# encoder.net
KiCad netlist of a schematic drawn in EAGLE
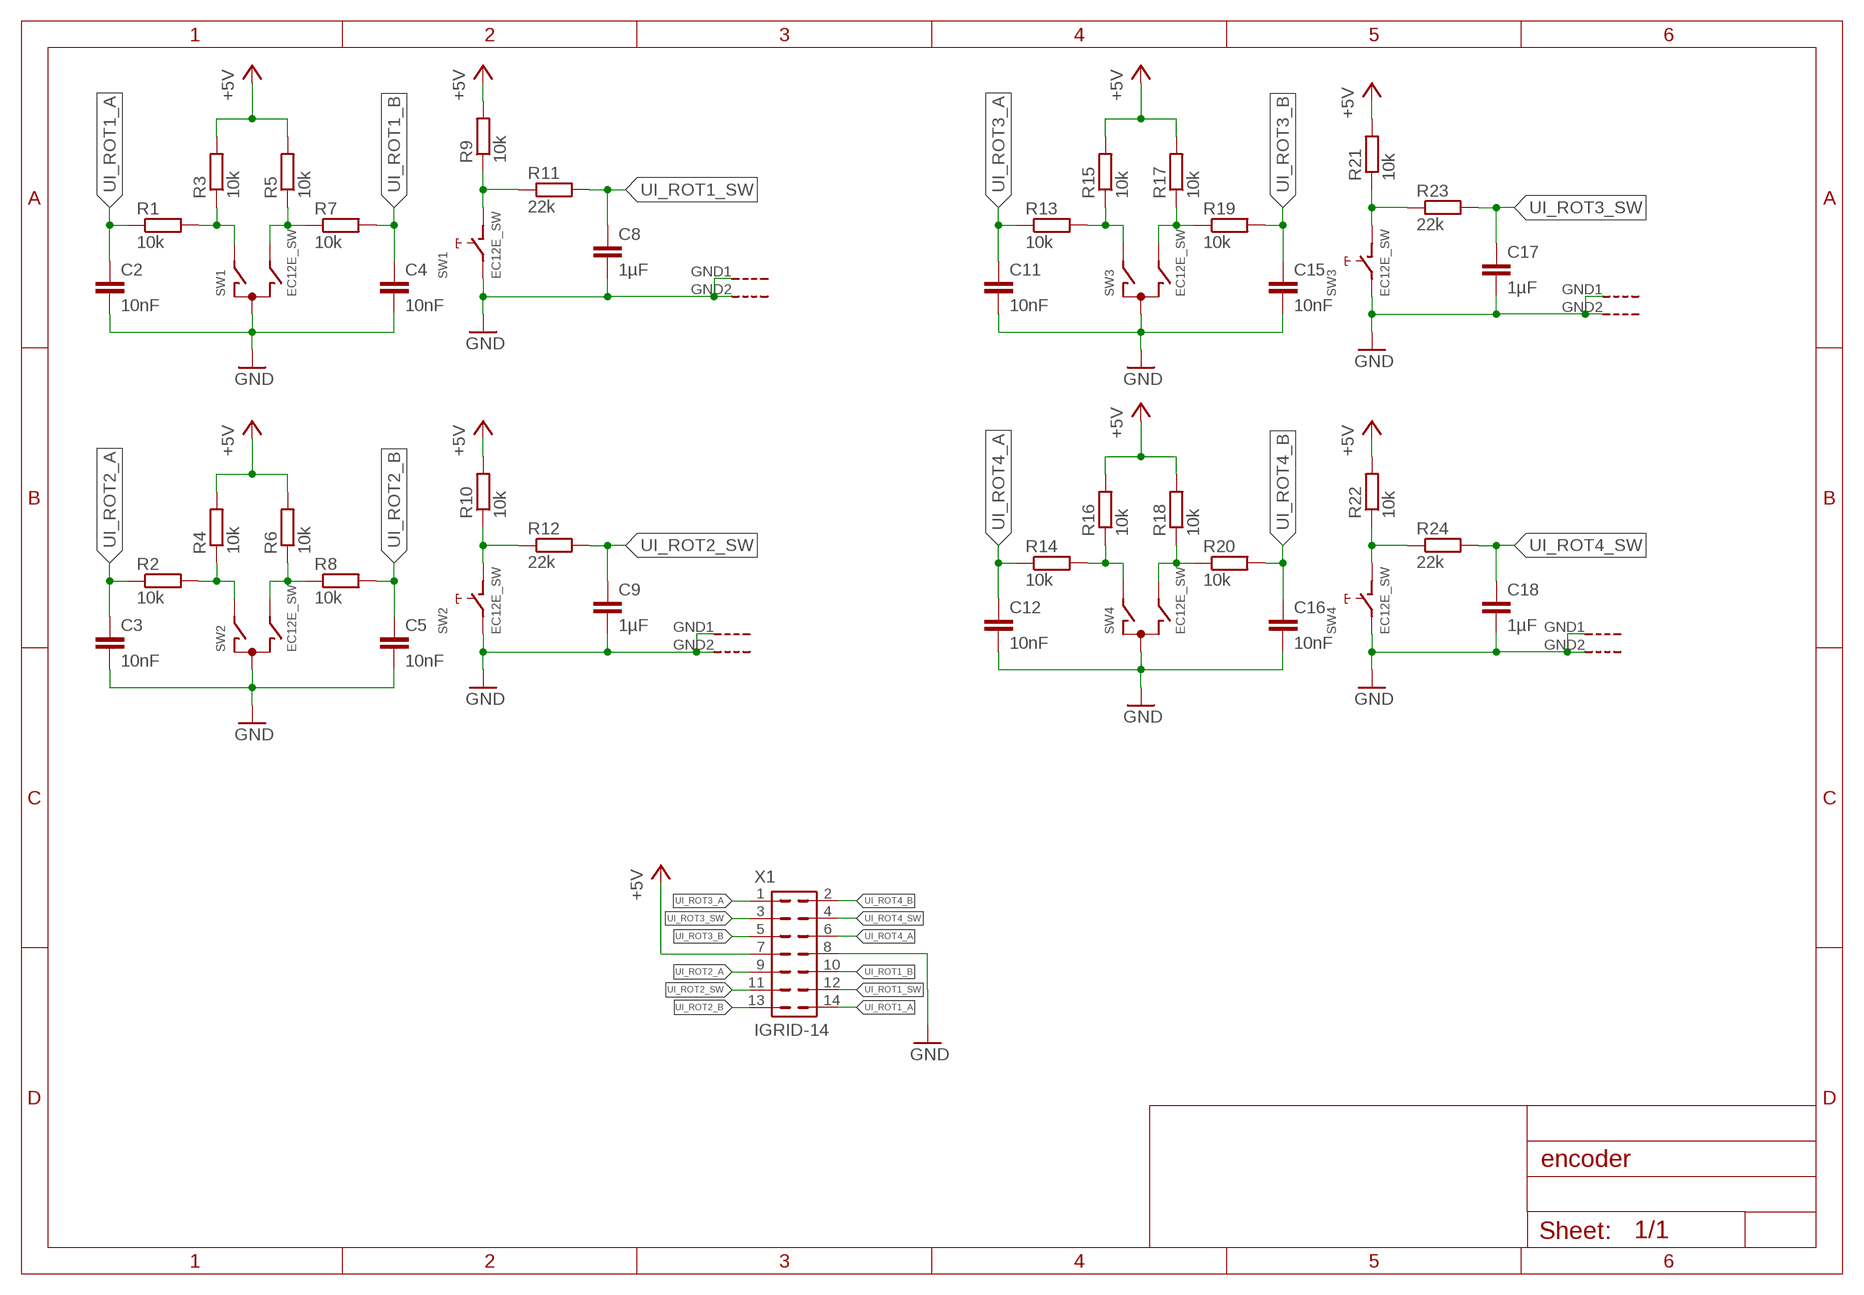
[diagram p0: schematic, sheet 1]

(export (version "E")
  (design (tool "Eeschema 10.0.6"))
  (components
    (comp (ref "C2")
      (value "10nF")
      (footprint "eagle-import:C0805")
      (libsource (lib "eagle-import") (part "C-EUC0805"))
    )
    (comp (ref "C3")
      (value "10nF")
      (footprint "eagle-import:C0805")
      (libsource (lib "eagle-import") (part "C-EUC0805"))
    )
    (comp (ref "C4")
      (value "10nF")
      (footprint "eagle-import:C0805")
      (libsource (lib "eagle-import") (part "C-EUC0805"))
    )
    (comp (ref "C5")
      (value "10nF")
      (footprint "eagle-import:C0805")
      (libsource (lib "eagle-import") (part "C-EUC0805"))
    )
    (comp (ref "C8")
      (value "1µF")
      (footprint "eagle-import:C0805")
      (libsource (lib "eagle-import") (part "C-EUC0805"))
    )
    (comp (ref "C9")
      (value "1µF")
      (footprint "eagle-import:C0805")
      (libsource (lib "eagle-import") (part "C-EUC0805"))
    )
    (comp (ref "C11")
      (value "10nF")
      (footprint "eagle-import:C0805")
      (libsource (lib "eagle-import") (part "C-EUC0805"))
    )
    (comp (ref "C12")
      (value "10nF")
      (footprint "eagle-import:C0805")
      (libsource (lib "eagle-import") (part "C-EUC0805"))
    )
    (comp (ref "C15")
      (value "10nF")
      (footprint "eagle-import:C0805")
      (libsource (lib "eagle-import") (part "C-EUC0805"))
    )
    (comp (ref "C16")
      (value "10nF")
      (footprint "eagle-import:C0805")
      (libsource (lib "eagle-import") (part "C-EUC0805"))
    )
    (comp (ref "C17")
      (value "1µF")
      (footprint "eagle-import:C0805")
      (libsource (lib "eagle-import") (part "C-EUC0805"))
    )
    (comp (ref "C18")
      (value "1µF")
      (footprint "eagle-import:C0805")
      (libsource (lib "eagle-import") (part "C-EUC0805"))
    )
    (comp (ref "R1")
      (value "10k")
      (footprint "eagle-import:R0805")
      (libsource (lib "eagle-import") (part "R-EU_R0805"))
    )
    (comp (ref "R2")
      (value "10k")
      (footprint "eagle-import:R0805")
      (libsource (lib "eagle-import") (part "R-EU_R0805"))
    )
    (comp (ref "R3")
      (value "10k")
      (footprint "eagle-import:R0805")
      (libsource (lib "eagle-import") (part "R-EU_R0805"))
    )
    (comp (ref "R4")
      (value "10k")
      (footprint "eagle-import:R0805")
      (libsource (lib "eagle-import") (part "R-EU_R0805"))
    )
    (comp (ref "R5")
      (value "10k")
      (footprint "eagle-import:R0805")
      (libsource (lib "eagle-import") (part "R-EU_R0805"))
    )
    (comp (ref "R6")
      (value "10k")
      (footprint "eagle-import:R0805")
      (libsource (lib "eagle-import") (part "R-EU_R0805"))
    )
    (comp (ref "R7")
      (value "10k")
      (footprint "eagle-import:R0805")
      (libsource (lib "eagle-import") (part "R-EU_R0805"))
    )
    (comp (ref "R8")
      (value "10k")
      (footprint "eagle-import:R0805")
      (libsource (lib "eagle-import") (part "R-EU_R0805"))
    )
    (comp (ref "R9")
      (value "10k")
      (footprint "eagle-import:R0805")
      (libsource (lib "eagle-import") (part "R-EU_R0805"))
    )
    (comp (ref "R10")
      (value "10k")
      (footprint "eagle-import:R0805")
      (libsource (lib "eagle-import") (part "R-EU_R0805"))
    )
    (comp (ref "R11")
      (value "22k")
      (footprint "eagle-import:R0805")
      (libsource (lib "eagle-import") (part "R-EU_R0805"))
    )
    (comp (ref "R12")
      (value "22k")
      (footprint "eagle-import:R0805")
      (libsource (lib "eagle-import") (part "R-EU_R0805"))
    )
    (comp (ref "R13")
      (value "10k")
      (footprint "eagle-import:R0805")
      (libsource (lib "eagle-import") (part "R-EU_R0805"))
    )
    (comp (ref "R14")
      (value "10k")
      (footprint "eagle-import:R0805")
      (libsource (lib "eagle-import") (part "R-EU_R0805"))
    )
    (comp (ref "R15")
      (value "10k")
      (footprint "eagle-import:R0805")
      (libsource (lib "eagle-import") (part "R-EU_R0805"))
    )
    (comp (ref "R16")
      (value "10k")
      (footprint "eagle-import:R0805")
      (libsource (lib "eagle-import") (part "R-EU_R0805"))
    )
    (comp (ref "R17")
      (value "10k")
      (footprint "eagle-import:R0805")
      (libsource (lib "eagle-import") (part "R-EU_R0805"))
    )
    (comp (ref "R18")
      (value "10k")
      (footprint "eagle-import:R0805")
      (libsource (lib "eagle-import") (part "R-EU_R0805"))
    )
    (comp (ref "R19")
      (value "10k")
      (footprint "eagle-import:R0805")
      (libsource (lib "eagle-import") (part "R-EU_R0805"))
    )
    (comp (ref "R20")
      (value "10k")
      (footprint "eagle-import:R0805")
      (libsource (lib "eagle-import") (part "R-EU_R0805"))
    )
    (comp (ref "R21")
      (value "10k")
      (footprint "eagle-import:R0805")
      (libsource (lib "eagle-import") (part "R-EU_R0805"))
    )
    (comp (ref "R22")
      (value "10k")
      (footprint "eagle-import:R0805")
      (libsource (lib "eagle-import") (part "R-EU_R0805"))
    )
    (comp (ref "R23")
      (value "22k")
      (footprint "eagle-import:R0805")
      (libsource (lib "eagle-import") (part "R-EU_R0805"))
    )
    (comp (ref "R24")
      (value "22k")
      (footprint "eagle-import:R0805")
      (libsource (lib "eagle-import") (part "R-EU_R0805"))
    )
    (comp (ref "SW1")
      (value "EC12E_SW")
      (footprint "eagle-import:ALPS_EC12E_SW")
      (fields (field (name "MPN") "EC12E2424407"))
      (libsource (lib "eagle-import") (part "EC12E_SW"))
    )
    (comp (ref "SW2")
      (value "EC12E_SW")
      (footprint "eagle-import:ALPS_EC12E_SW")
      (fields (field (name "MPN") "EC12E2424407"))
      (libsource (lib "eagle-import") (part "EC12E_SW"))
    )
    (comp (ref "SW3")
      (value "EC12E_SW")
      (footprint "eagle-import:ALPS_EC12E_SW")
      (fields (field (name "MPN") "EC12E2424407"))
      (libsource (lib "eagle-import") (part "EC12E_SW"))
    )
    (comp (ref "SW4")
      (value "EC12E_SW")
      (footprint "eagle-import:ALPS_EC12E_SW")
      (fields (field (name "MPN") "EC12E2424407"))
      (libsource (lib "eagle-import") (part "EC12E_SW"))
    )
    (comp (ref "X1")
      (value "IGRID-14")
      (footprint "eagle-import:I-GRID-14")
      (libsource (lib "eagle-import") (part "IGRID-14"))
    )
  )
  (nets
    (net (code "1") (name "+5V") (class "Default")
      (node (ref "R10") (pin "2") (pinfunction "2_2") (pintype "passive"))
      (node (ref "R15") (pin "2") (pinfunction "2_2") (pintype "passive"))
      (node (ref "R16") (pin "2") (pinfunction "2_2") (pintype "passive"))
      (node (ref "R17") (pin "2") (pinfunction "2_2") (pintype "passive"))
      (node (ref "R18") (pin "2") (pinfunction "2_2") (pintype "passive"))
      (node (ref "R21") (pin "2") (pinfunction "2_2") (pintype "passive"))
      (node (ref "R22") (pin "2") (pinfunction "2_2") (pintype "passive"))
      (node (ref "R3") (pin "2") (pinfunction "2_2") (pintype "passive"))
      (node (ref "R4") (pin "2") (pinfunction "2_2") (pintype "passive"))
      (node (ref "R5") (pin "2") (pinfunction "2_2") (pintype "passive"))
      (node (ref "R6") (pin "2") (pinfunction "2_2") (pintype "passive"))
      (node (ref "R9") (pin "2") (pinfunction "2_2") (pintype "passive"))
      (node (ref "X1") (pin "7") (pinfunction "7_7") (pintype "passive"))
    )
    (net (code "2") (name "GND") (class "Default")
      (node (ref "C11") (pin "2") (pinfunction "2_2") (pintype "passive"))
      (node (ref "C12") (pin "2") (pinfunction "2_2") (pintype "passive"))
      (node (ref "C15") (pin "2") (pinfunction "2_2") (pintype "passive"))
      (node (ref "C16") (pin "2") (pinfunction "2_2") (pintype "passive"))
      (node (ref "C17") (pin "2") (pinfunction "2_2") (pintype "passive"))
      (node (ref "C18") (pin "2") (pinfunction "2_2") (pintype "passive"))
      (node (ref "C2") (pin "2") (pinfunction "2_2") (pintype "passive"))
      (node (ref "C3") (pin "2") (pinfunction "2_2") (pintype "passive"))
      (node (ref "C4") (pin "2") (pinfunction "2_2") (pintype "passive"))
      (node (ref "C5") (pin "2") (pinfunction "2_2") (pintype "passive"))
      (node (ref "C8") (pin "2") (pinfunction "2_2") (pintype "passive"))
      (node (ref "C9") (pin "2") (pinfunction "2_2") (pintype "passive"))
      (node (ref "SW1") (pin "C") (pinfunction "C_C") (pintype "passive"))
      (node (ref "SW1") (pin "E") (pinfunction "2_E") (pintype "passive"))
      (node (ref "SW1") (pin "GND1") (pinfunction "G_GND1") (pintype "passive"))
      (node (ref "SW1") (pin "GND2") (pinfunction "G_GND2") (pintype "passive"))
      (node (ref "SW2") (pin "C") (pinfunction "C_C") (pintype "passive"))
      (node (ref "SW2") (pin "E") (pinfunction "2_E") (pintype "passive"))
      (node (ref "SW2") (pin "GND1") (pinfunction "G_GND1") (pintype "passive"))
      (node (ref "SW2") (pin "GND2") (pinfunction "G_GND2") (pintype "passive"))
      (node (ref "SW3") (pin "C") (pinfunction "C_C") (pintype "passive"))
      (node (ref "SW3") (pin "E") (pinfunction "2_E") (pintype "passive"))
      (node (ref "SW3") (pin "GND1") (pinfunction "G_GND1") (pintype "passive"))
      (node (ref "SW3") (pin "GND2") (pinfunction "G_GND2") (pintype "passive"))
      (node (ref "SW4") (pin "C") (pinfunction "C_C") (pintype "passive"))
      (node (ref "SW4") (pin "E") (pinfunction "2_E") (pintype "passive"))
      (node (ref "SW4") (pin "GND1") (pinfunction "G_GND1") (pintype "passive"))
      (node (ref "SW4") (pin "GND2") (pinfunction "G_GND2") (pintype "passive"))
      (node (ref "X1") (pin "8") (pinfunction "8_8") (pintype "passive"))
    )
    (net (code "3") (name "Net-(R1-Pad2)") (class "Default")
      (node (ref "R1") (pin "2") (pinfunction "2_2") (pintype "passive"))
      (node (ref "R3") (pin "1") (pinfunction "1_1") (pintype "passive"))
      (node (ref "SW1") (pin "A") (pinfunction "A_A") (pintype "passive"))
    )
    (net (code "4") (name "Net-(R2-Pad2)") (class "Default")
      (node (ref "R2") (pin "2") (pinfunction "2_2") (pintype "passive"))
      (node (ref "R4") (pin "1") (pinfunction "1_1") (pintype "passive"))
      (node (ref "SW2") (pin "A") (pinfunction "A_A") (pintype "passive"))
    )
    (net (code "5") (name "Net-(R5-Pad1)") (class "Default")
      (node (ref "R5") (pin "1") (pinfunction "1_1") (pintype "passive"))
      (node (ref "R7") (pin "1") (pinfunction "1_1") (pintype "passive"))
      (node (ref "SW1") (pin "B") (pinfunction "B_B") (pintype "passive"))
    )
    (net (code "6") (name "Net-(R6-Pad1)") (class "Default")
      (node (ref "R6") (pin "1") (pinfunction "1_1") (pintype "passive"))
      (node (ref "R8") (pin "1") (pinfunction "1_1") (pintype "passive"))
      (node (ref "SW2") (pin "B") (pinfunction "B_B") (pintype "passive"))
    )
    (net (code "7") (name "Net-(R13-Pad2)") (class "Default")
      (node (ref "R13") (pin "2") (pinfunction "2_2") (pintype "passive"))
      (node (ref "R15") (pin "1") (pinfunction "1_1") (pintype "passive"))
      (node (ref "SW3") (pin "A") (pinfunction "A_A") (pintype "passive"))
    )
    (net (code "8") (name "Net-(R14-Pad2)") (class "Default")
      (node (ref "R14") (pin "2") (pinfunction "2_2") (pintype "passive"))
      (node (ref "R16") (pin "1") (pinfunction "1_1") (pintype "passive"))
      (node (ref "SW4") (pin "A") (pinfunction "A_A") (pintype "passive"))
    )
    (net (code "9") (name "Net-(R17-Pad1)") (class "Default")
      (node (ref "R17") (pin "1") (pinfunction "1_1") (pintype "passive"))
      (node (ref "R19") (pin "1") (pinfunction "1_1") (pintype "passive"))
      (node (ref "SW3") (pin "B") (pinfunction "B_B") (pintype "passive"))
    )
    (net (code "10") (name "Net-(R18-Pad1)") (class "Default")
      (node (ref "R18") (pin "1") (pinfunction "1_1") (pintype "passive"))
      (node (ref "R20") (pin "1") (pinfunction "1_1") (pintype "passive"))
      (node (ref "SW4") (pin "B") (pinfunction "B_B") (pintype "passive"))
    )
    (net (code "11") (name "Net-(SW1B-1)") (class "Default")
      (node (ref "R11") (pin "1") (pinfunction "1_1") (pintype "passive"))
      (node (ref "R9") (pin "1") (pinfunction "1_1") (pintype "passive"))
      (node (ref "SW1") (pin "D") (pinfunction "1_D") (pintype "passive"))
    )
    (net (code "12") (name "Net-(SW2B-1)") (class "Default")
      (node (ref "R10") (pin "1") (pinfunction "1_1") (pintype "passive"))
      (node (ref "R12") (pin "1") (pinfunction "1_1") (pintype "passive"))
      (node (ref "SW2") (pin "D") (pinfunction "1_D") (pintype "passive"))
    )
    (net (code "13") (name "Net-(SW3B-1)") (class "Default")
      (node (ref "R21") (pin "1") (pinfunction "1_1") (pintype "passive"))
      (node (ref "R23") (pin "1") (pinfunction "1_1") (pintype "passive"))
      (node (ref "SW3") (pin "D") (pinfunction "1_D") (pintype "passive"))
    )
    (net (code "14") (name "Net-(SW4B-1)") (class "Default")
      (node (ref "R22") (pin "1") (pinfunction "1_1") (pintype "passive"))
      (node (ref "R24") (pin "1") (pinfunction "1_1") (pintype "passive"))
      (node (ref "SW4") (pin "D") (pinfunction "1_D") (pintype "passive"))
    )
    (net (code "15") (name "UI_ROT1_A") (class "Default")
      (node (ref "C2") (pin "1") (pinfunction "1_1") (pintype "passive"))
      (node (ref "R1") (pin "1") (pinfunction "1_1") (pintype "passive"))
      (node (ref "X1") (pin "14") (pinfunction "14_14") (pintype "passive"))
    )
    (net (code "16") (name "UI_ROT1_B") (class "Default")
      (node (ref "C4") (pin "1") (pinfunction "1_1") (pintype "passive"))
      (node (ref "R7") (pin "2") (pinfunction "2_2") (pintype "passive"))
      (node (ref "X1") (pin "10") (pinfunction "10_10") (pintype "passive"))
    )
    (net (code "17") (name "UI_ROT1_SW") (class "Default")
      (node (ref "C8") (pin "1") (pinfunction "1_1") (pintype "passive"))
      (node (ref "R11") (pin "2") (pinfunction "2_2") (pintype "passive"))
      (node (ref "X1") (pin "12") (pinfunction "12_12") (pintype "passive"))
    )
    (net (code "18") (name "UI_ROT2_A") (class "Default")
      (node (ref "C3") (pin "1") (pinfunction "1_1") (pintype "passive"))
      (node (ref "R2") (pin "1") (pinfunction "1_1") (pintype "passive"))
      (node (ref "X1") (pin "9") (pinfunction "9_9") (pintype "passive"))
    )
    (net (code "19") (name "UI_ROT2_B") (class "Default")
      (node (ref "C5") (pin "1") (pinfunction "1_1") (pintype "passive"))
      (node (ref "R8") (pin "2") (pinfunction "2_2") (pintype "passive"))
      (node (ref "X1") (pin "13") (pinfunction "13_13") (pintype "passive"))
    )
    (net (code "20") (name "UI_ROT2_SW") (class "Default")
      (node (ref "C9") (pin "1") (pinfunction "1_1") (pintype "passive"))
      (node (ref "R12") (pin "2") (pinfunction "2_2") (pintype "passive"))
      (node (ref "X1") (pin "11") (pinfunction "11_11") (pintype "passive"))
    )
    (net (code "21") (name "UI_ROT3_A") (class "Default")
      (node (ref "C11") (pin "1") (pinfunction "1_1") (pintype "passive"))
      (node (ref "R13") (pin "1") (pinfunction "1_1") (pintype "passive"))
      (node (ref "X1") (pin "1") (pinfunction "1_1") (pintype "passive"))
    )
    (net (code "22") (name "UI_ROT3_B") (class "Default")
      (node (ref "C15") (pin "1") (pinfunction "1_1") (pintype "passive"))
      (node (ref "R19") (pin "2") (pinfunction "2_2") (pintype "passive"))
      (node (ref "X1") (pin "5") (pinfunction "5_5") (pintype "passive"))
    )
    (net (code "23") (name "UI_ROT3_SW") (class "Default")
      (node (ref "C17") (pin "1") (pinfunction "1_1") (pintype "passive"))
      (node (ref "R23") (pin "2") (pinfunction "2_2") (pintype "passive"))
      (node (ref "X1") (pin "3") (pinfunction "3_3") (pintype "passive"))
    )
    (net (code "24") (name "UI_ROT4_A") (class "Default")
      (node (ref "C12") (pin "1") (pinfunction "1_1") (pintype "passive"))
      (node (ref "R14") (pin "1") (pinfunction "1_1") (pintype "passive"))
      (node (ref "X1") (pin "6") (pinfunction "6_6") (pintype "passive"))
    )
    (net (code "25") (name "UI_ROT4_B") (class "Default")
      (node (ref "C16") (pin "1") (pinfunction "1_1") (pintype "passive"))
      (node (ref "R20") (pin "2") (pinfunction "2_2") (pintype "passive"))
      (node (ref "X1") (pin "2") (pinfunction "2_2") (pintype "passive"))
    )
    (net (code "26") (name "UI_ROT4_SW") (class "Default")
      (node (ref "C18") (pin "1") (pinfunction "1_1") (pintype "passive"))
      (node (ref "R24") (pin "2") (pinfunction "2_2") (pintype "passive"))
      (node (ref "X1") (pin "4") (pinfunction "4_4") (pintype "passive"))
    )
  )
)
